# SCH_orbital_shaker_motherboard_v2_2022-0.net
KiCad netlist of a schematic drawn in EasyEDA
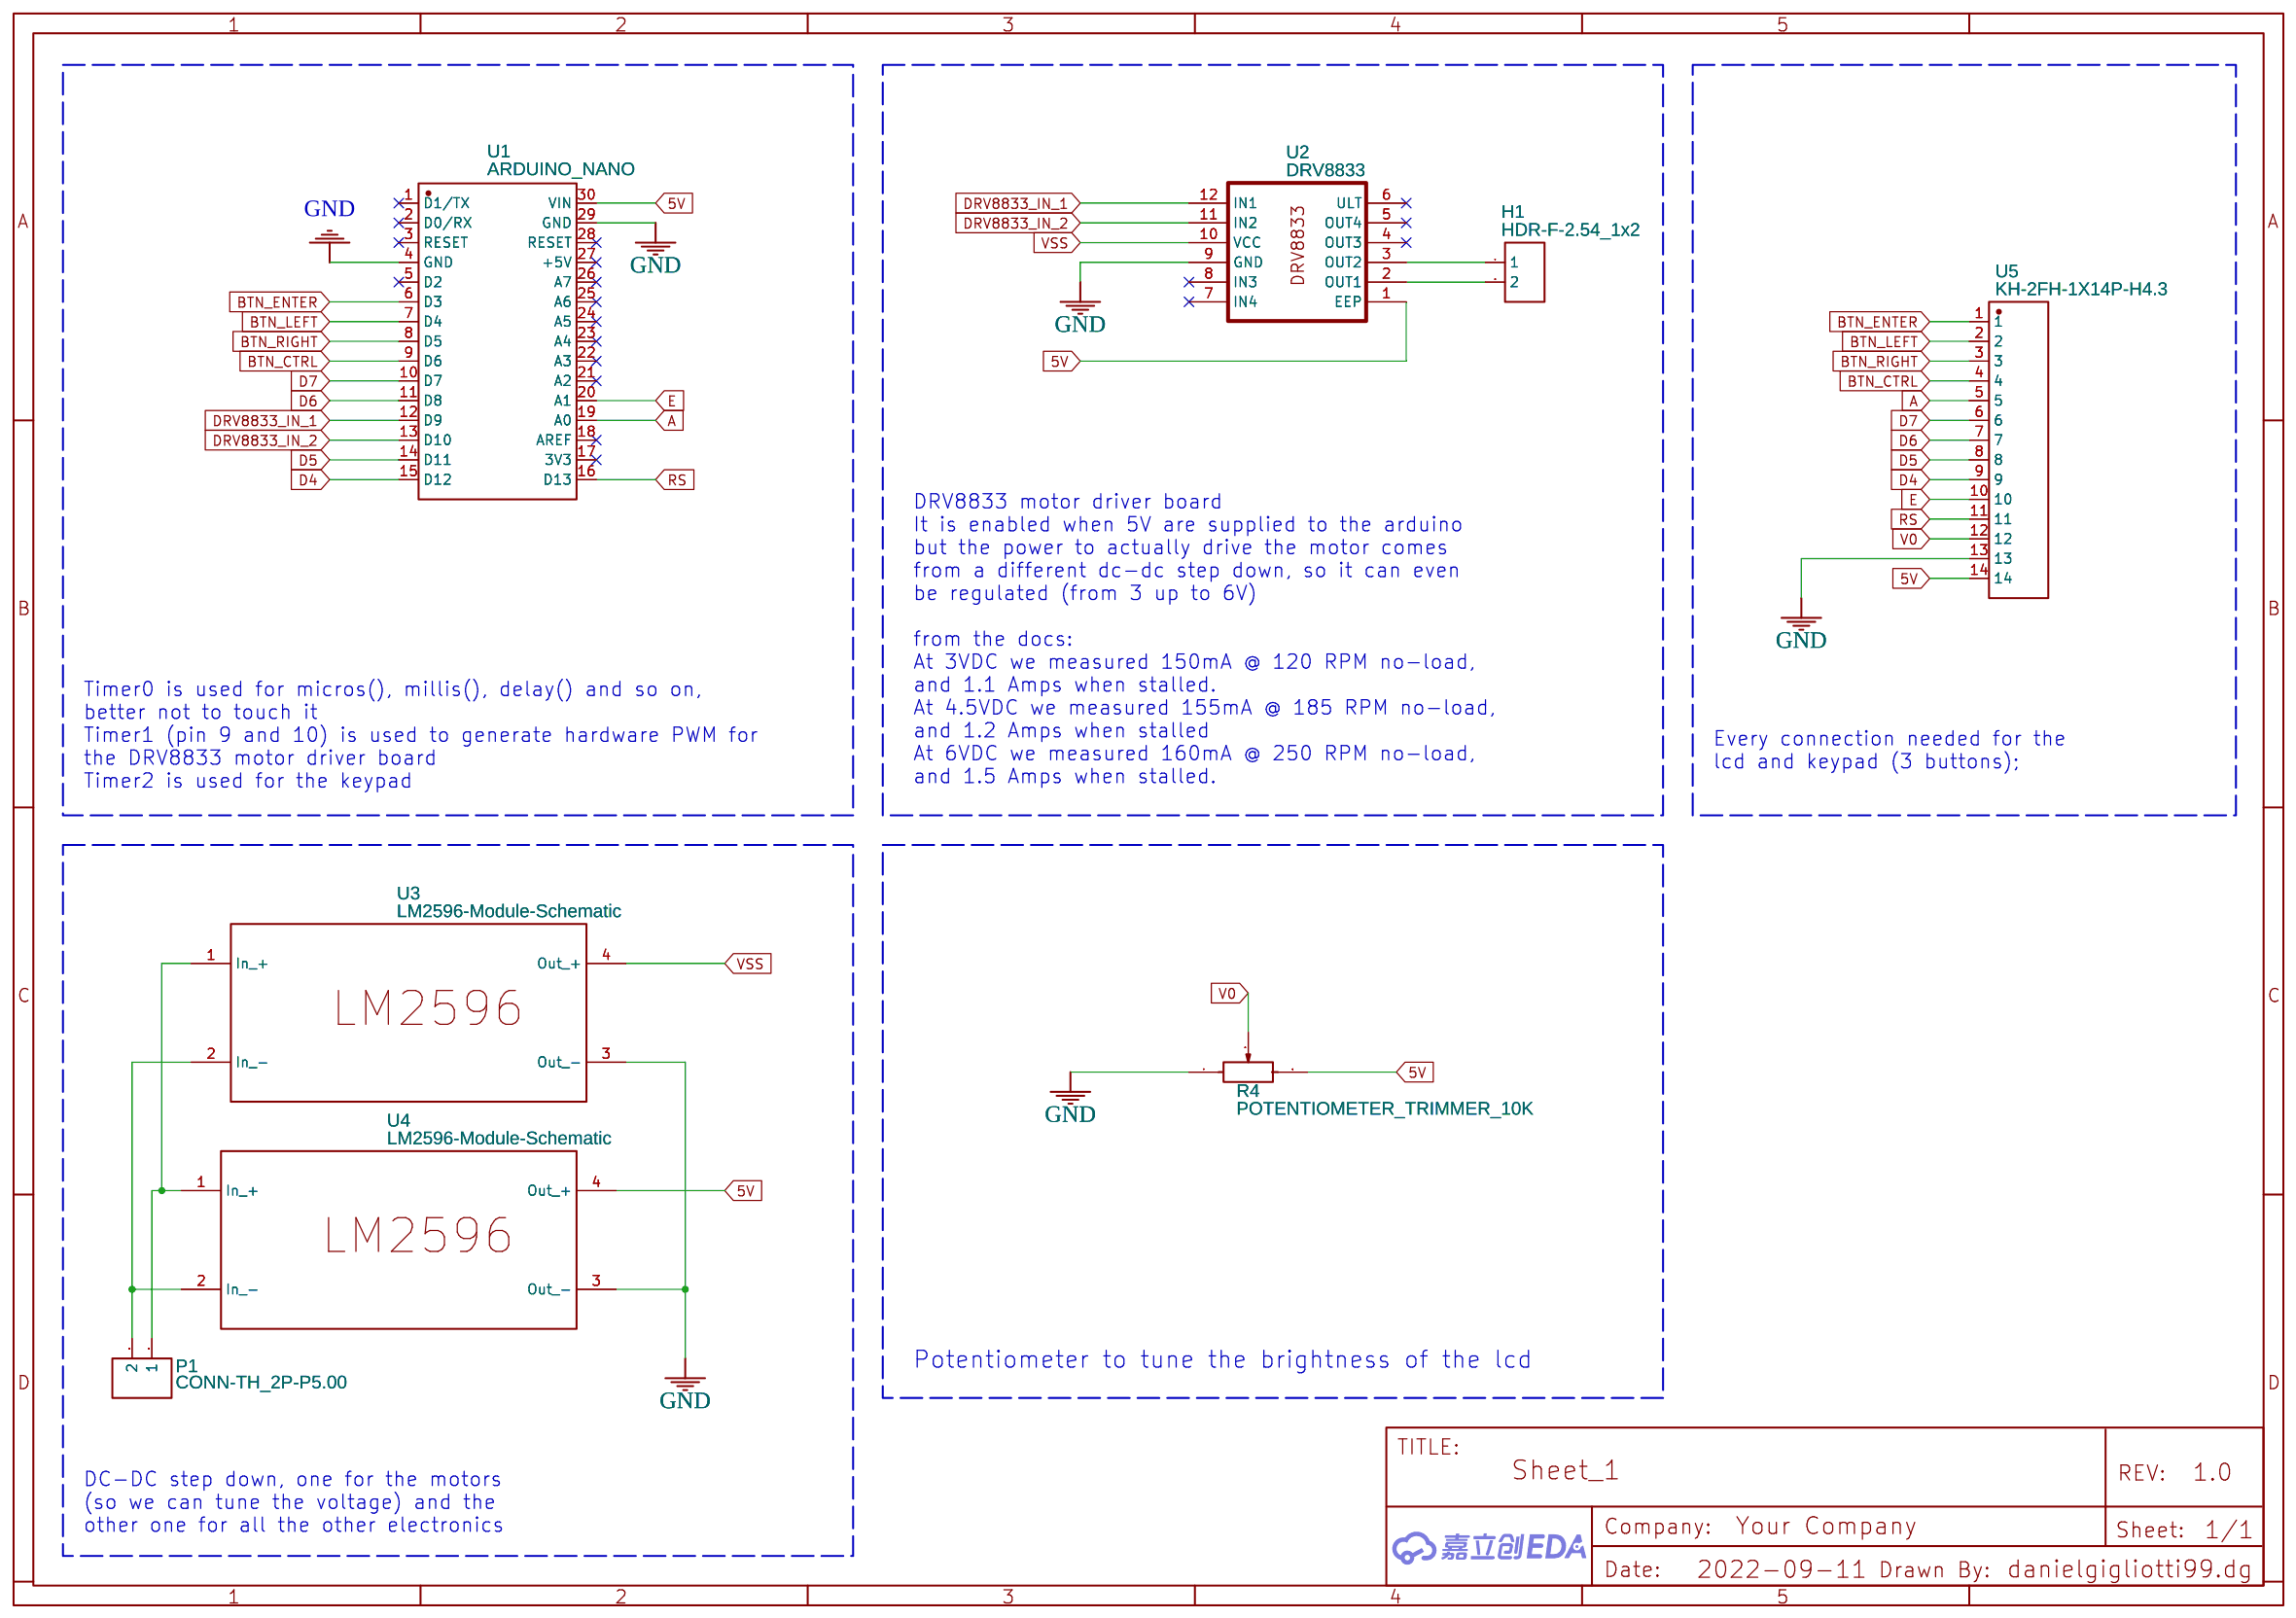
[diagram p0: schematic sheet]

(export (version "E")
  (design (tool "Eeschema 10.0.6"))
  (components
    (comp (ref "H1")
      (value "HDR-F-2.54_1x2")
      (fields (field (name "BOM_Supplier Part") "C49661"))
      (libsource (lib "") (part "HDR-F-2.54_1x2"))
    )
    (comp (ref "P1") (value "CONN-TH_2P-P5.00") (libsource (lib "") (part "CONN-TH_2P-P5.00")))
    (comp (ref "R4")
      (value "POTENTIOMETER_TRIMMER_10K")
      (libsource (lib "") (part "POTENTIOMETER_TRIMMER_10K"))
    )
    (comp (ref "U1")
      (value "ARDUINO_NANO")
      (fields (field (name "BOM_Supplier Part") "C9900017879"))
      (libsource (lib "") (part "ARDUINO_NANO"))
    )
    (comp (ref "U2") (value "DRV8833") (libsource (lib "") (part "DRV8833 (NO ORIGINAL)")))
    (comp (ref "U3") (value "LM2596-Module-Schematic") (libsource (lib "") (part "LM2596-Module-Schematic")))
    (comp (ref "U4") (value "LM2596-Module-Schematic") (libsource (lib "") (part "LM2596-Module-Schematic")))
    (comp (ref "U5")
      (value "KH-2FH-1X14P-H4.3")
      (fields (field (name "BOM_Supplier Part") "C2938436"))
      (libsource (lib "") (part "KH-2FH-1X14P-H4.3"))
    )
  )
  (nets
    (net (code "1") (name "5V") (class "Default")
      (node (ref "R4") (pin "3") (pintype "unspecified"))
      (node (ref "U1") (pin "30") (pinfunction "VIN_30") (pintype "unspecified"))
      (node (ref "U2") (pin "1") (pinfunction "EEP_1") (pintype "unspecified"))
      (node (ref "U4") (pin "4") (pinfunction "Out_+_4") (pintype "unspecified"))
      (node (ref "U5") (pin "14") (pinfunction "14_14") (pintype "unspecified"))
    )
    (net (code "2") (name "A") (class "Default")
      (node (ref "U1") (pin "19") (pinfunction "A0_19") (pintype "unspecified"))
      (node (ref "U5") (pin "5") (pinfunction "5_5") (pintype "unspecified"))
    )
    (net (code "3") (name "BTN_CTRL") (class "Default")
      (node (ref "U1") (pin "9") (pinfunction "D6_9") (pintype "unspecified"))
      (node (ref "U5") (pin "4") (pinfunction "4_4") (pintype "unspecified"))
    )
    (net (code "4") (name "BTN_ENTER") (class "Default")
      (node (ref "U1") (pin "6") (pinfunction "D3_6") (pintype "unspecified"))
      (node (ref "U5") (pin "1") (pinfunction "1_1") (pintype "unspecified"))
    )
    (net (code "5") (name "BTN_LEFT") (class "Default")
      (node (ref "U1") (pin "7") (pinfunction "D4_7") (pintype "unspecified"))
      (node (ref "U5") (pin "2") (pinfunction "2_2") (pintype "unspecified"))
    )
    (net (code "6") (name "BTN_RIGHT") (class "Default")
      (node (ref "U1") (pin "8") (pinfunction "D5_8") (pintype "unspecified"))
      (node (ref "U5") (pin "3") (pinfunction "3_3") (pintype "unspecified"))
    )
    (net (code "7") (name "D4") (class "Default")
      (node (ref "U1") (pin "15") (pinfunction "D12_15") (pintype "unspecified"))
      (node (ref "U5") (pin "9") (pinfunction "9_9") (pintype "unspecified"))
    )
    (net (code "8") (name "D5") (class "Default")
      (node (ref "U1") (pin "14") (pinfunction "D11_14") (pintype "unspecified"))
      (node (ref "U5") (pin "8") (pinfunction "8_8") (pintype "unspecified"))
    )
    (net (code "9") (name "D6") (class "Default")
      (node (ref "U1") (pin "11") (pinfunction "D8_11") (pintype "unspecified"))
      (node (ref "U5") (pin "7") (pinfunction "7_7") (pintype "unspecified"))
    )
    (net (code "10") (name "D7") (class "Default")
      (node (ref "U1") (pin "10") (pinfunction "D7_10") (pintype "unspecified"))
      (node (ref "U5") (pin "6") (pinfunction "6_6") (pintype "unspecified"))
    )
    (net (code "11") (name "DRV8833_IN_1") (class "Default")
      (node (ref "U1") (pin "12") (pinfunction "D9_12") (pintype "unspecified"))
      (node (ref "U2") (pin "12") (pinfunction "IN1_12") (pintype "unspecified"))
    )
    (net (code "12") (name "DRV8833_IN_2") (class "Default")
      (node (ref "U1") (pin "13") (pinfunction "D10_13") (pintype "unspecified"))
      (node (ref "U2") (pin "11") (pinfunction "IN2_11") (pintype "unspecified"))
    )
    (net (code "13") (name "E") (class "Default")
      (node (ref "U1") (pin "20") (pinfunction "A1_20") (pintype "unspecified"))
      (node (ref "U5") (pin "10") (pinfunction "10_10") (pintype "unspecified"))
    )
    (net (code "14") (name "GND") (class "Default")
      (node (ref "R4") (pin "1") (pintype "unspecified"))
      (node (ref "U1") (pin "29") (pinfunction "GND_29") (pintype "unspecified"))
      (node (ref "U1") (pin "4") (pinfunction "GND_4") (pintype "unspecified"))
      (node (ref "U2") (pin "9") (pinfunction "GND_9") (pintype "unspecified"))
      (node (ref "U3") (pin "3") (pinfunction "Out_-_3") (pintype "unspecified"))
      (node (ref "U4") (pin "3") (pinfunction "Out_-_3") (pintype "unspecified"))
      (node (ref "U5") (pin "13") (pinfunction "13_13") (pintype "unspecified"))
    )
    (net (code "15") (name "Net-(U2-OUT1)") (class "Default")
      (node (ref "H1") (pin "2") (pinfunction "2_2") (pintype "input"))
      (node (ref "U2") (pin "2") (pinfunction "OUT1_2") (pintype "unspecified"))
    )
    (net (code "16") (name "Net-(U2-OUT2)") (class "Default")
      (node (ref "H1") (pin "1") (pinfunction "1_1") (pintype "input"))
      (node (ref "U2") (pin "3") (pinfunction "OUT2_3") (pintype "unspecified"))
    )
    (net (code "17") (name "Net-(U3-In_+)") (class "Default")
      (node (ref "P1") (pin "1") (pinfunction "1_1") (pintype "unspecified"))
      (node (ref "U3") (pin "1") (pinfunction "In_+_1") (pintype "unspecified"))
      (node (ref "U4") (pin "1") (pinfunction "In_+_1") (pintype "unspecified"))
    )
    (net (code "18") (name "Net-(U3-In_-)") (class "Default")
      (node (ref "P1") (pin "2") (pinfunction "2_2") (pintype "unspecified"))
      (node (ref "U3") (pin "2") (pinfunction "In_-_2") (pintype "unspecified"))
      (node (ref "U4") (pin "2") (pinfunction "In_-_2") (pintype "unspecified"))
    )
    (net (code "19") (name "RS") (class "Default")
      (node (ref "U1") (pin "16") (pinfunction "D13_16") (pintype "unspecified"))
      (node (ref "U5") (pin "11") (pinfunction "11_11") (pintype "unspecified"))
    )
    (net (code "20") (name "V0") (class "Default")
      (node (ref "R4") (pin "2") (pintype "unspecified"))
      (node (ref "U5") (pin "12") (pinfunction "12_12") (pintype "unspecified"))
    )
    (net (code "21") (name "VSS") (class "Default")
      (node (ref "U2") (pin "10") (pinfunction "VCC_10") (pintype "unspecified"))
      (node (ref "U3") (pin "4") (pinfunction "Out_+_4") (pintype "unspecified"))
    )
    (net (code "22") (name "unconnected-(U1-+5V-Pad27)") (class "Default")
      (node (ref "U1") (pin "27") (pinfunction "+5V_27") (pintype "unspecified+no_connect"))
    )
    (net (code "23") (name "unconnected-(U1-3V3-Pad17)") (class "Default")
      (node (ref "U1") (pin "17") (pinfunction "3V3_17") (pintype "unspecified+no_connect"))
    )
    (net (code "24") (name "unconnected-(U1-A2-Pad21)") (class "Default")
      (node (ref "U1") (pin "21") (pinfunction "A2_21") (pintype "unspecified+no_connect"))
    )
    (net (code "25") (name "unconnected-(U1-A3-Pad22)") (class "Default")
      (node (ref "U1") (pin "22") (pinfunction "A3_22") (pintype "unspecified+no_connect"))
    )
    (net (code "26") (name "unconnected-(U1-A4-Pad23)") (class "Default")
      (node (ref "U1") (pin "23") (pinfunction "A4_23") (pintype "unspecified+no_connect"))
    )
    (net (code "27") (name "unconnected-(U1-A5-Pad24)") (class "Default")
      (node (ref "U1") (pin "24") (pinfunction "A5_24") (pintype "unspecified+no_connect"))
    )
    (net (code "28") (name "unconnected-(U1-A6-Pad25)") (class "Default")
      (node (ref "U1") (pin "25") (pinfunction "A6_25") (pintype "unspecified+no_connect"))
    )
    (net (code "29") (name "unconnected-(U1-A7-Pad26)") (class "Default")
      (node (ref "U1") (pin "26") (pinfunction "A7_26") (pintype "unspecified+no_connect"))
    )
    (net (code "30") (name "unconnected-(U1-AREF-Pad18)") (class "Default")
      (node (ref "U1") (pin "18") (pinfunction "AREF_18") (pintype "unspecified+no_connect"))
    )
    (net (code "31") (name "unconnected-(U1-D0{slash}RX-Pad2)") (class "Default")
      (node (ref "U1") (pin "2") (pinfunction "D0/RX_2") (pintype "unspecified+no_connect"))
    )
    (net (code "32") (name "unconnected-(U1-D1{slash}TX-Pad1)") (class "Default")
      (node (ref "U1") (pin "1") (pinfunction "D1/TX_1") (pintype "unspecified+no_connect"))
    )
    (net (code "33") (name "unconnected-(U1-D2-Pad5)") (class "Default")
      (node (ref "U1") (pin "5") (pinfunction "D2_5") (pintype "unspecified+no_connect"))
    )
    (net (code "34") (name "unconnected-(U1-RESET-Pad3)") (class "Default")
      (node (ref "U1") (pin "3") (pinfunction "RESET_3") (pintype "unspecified+no_connect"))
    )
    (net (code "35") (name "unconnected-(U1-RESET-Pad28)") (class "Default")
      (node (ref "U1") (pin "28") (pinfunction "RESET_28") (pintype "unspecified+no_connect"))
    )
    (net (code "36") (name "unconnected-(U2-IN3-Pad8)") (class "Default")
      (node (ref "U2") (pin "8") (pinfunction "IN3_8") (pintype "unspecified+no_connect"))
    )
    (net (code "37") (name "unconnected-(U2-IN4-Pad7)") (class "Default")
      (node (ref "U2") (pin "7") (pinfunction "IN4_7") (pintype "unspecified+no_connect"))
    )
    (net (code "38") (name "unconnected-(U2-OUT3-Pad4)") (class "Default")
      (node (ref "U2") (pin "4") (pinfunction "OUT3_4") (pintype "unspecified+no_connect"))
    )
    (net (code "39") (name "unconnected-(U2-OUT4-Pad5)") (class "Default")
      (node (ref "U2") (pin "5") (pinfunction "OUT4_5") (pintype "unspecified+no_connect"))
    )
    (net (code "40") (name "unconnected-(U2-ULT-Pad6)") (class "Default")
      (node (ref "U2") (pin "6") (pinfunction "ULT_6") (pintype "unspecified+no_connect"))
    )
  )
)
